# RTI-RoR-wire.net
KiCad netlist of a schematic drawn in EAGLE
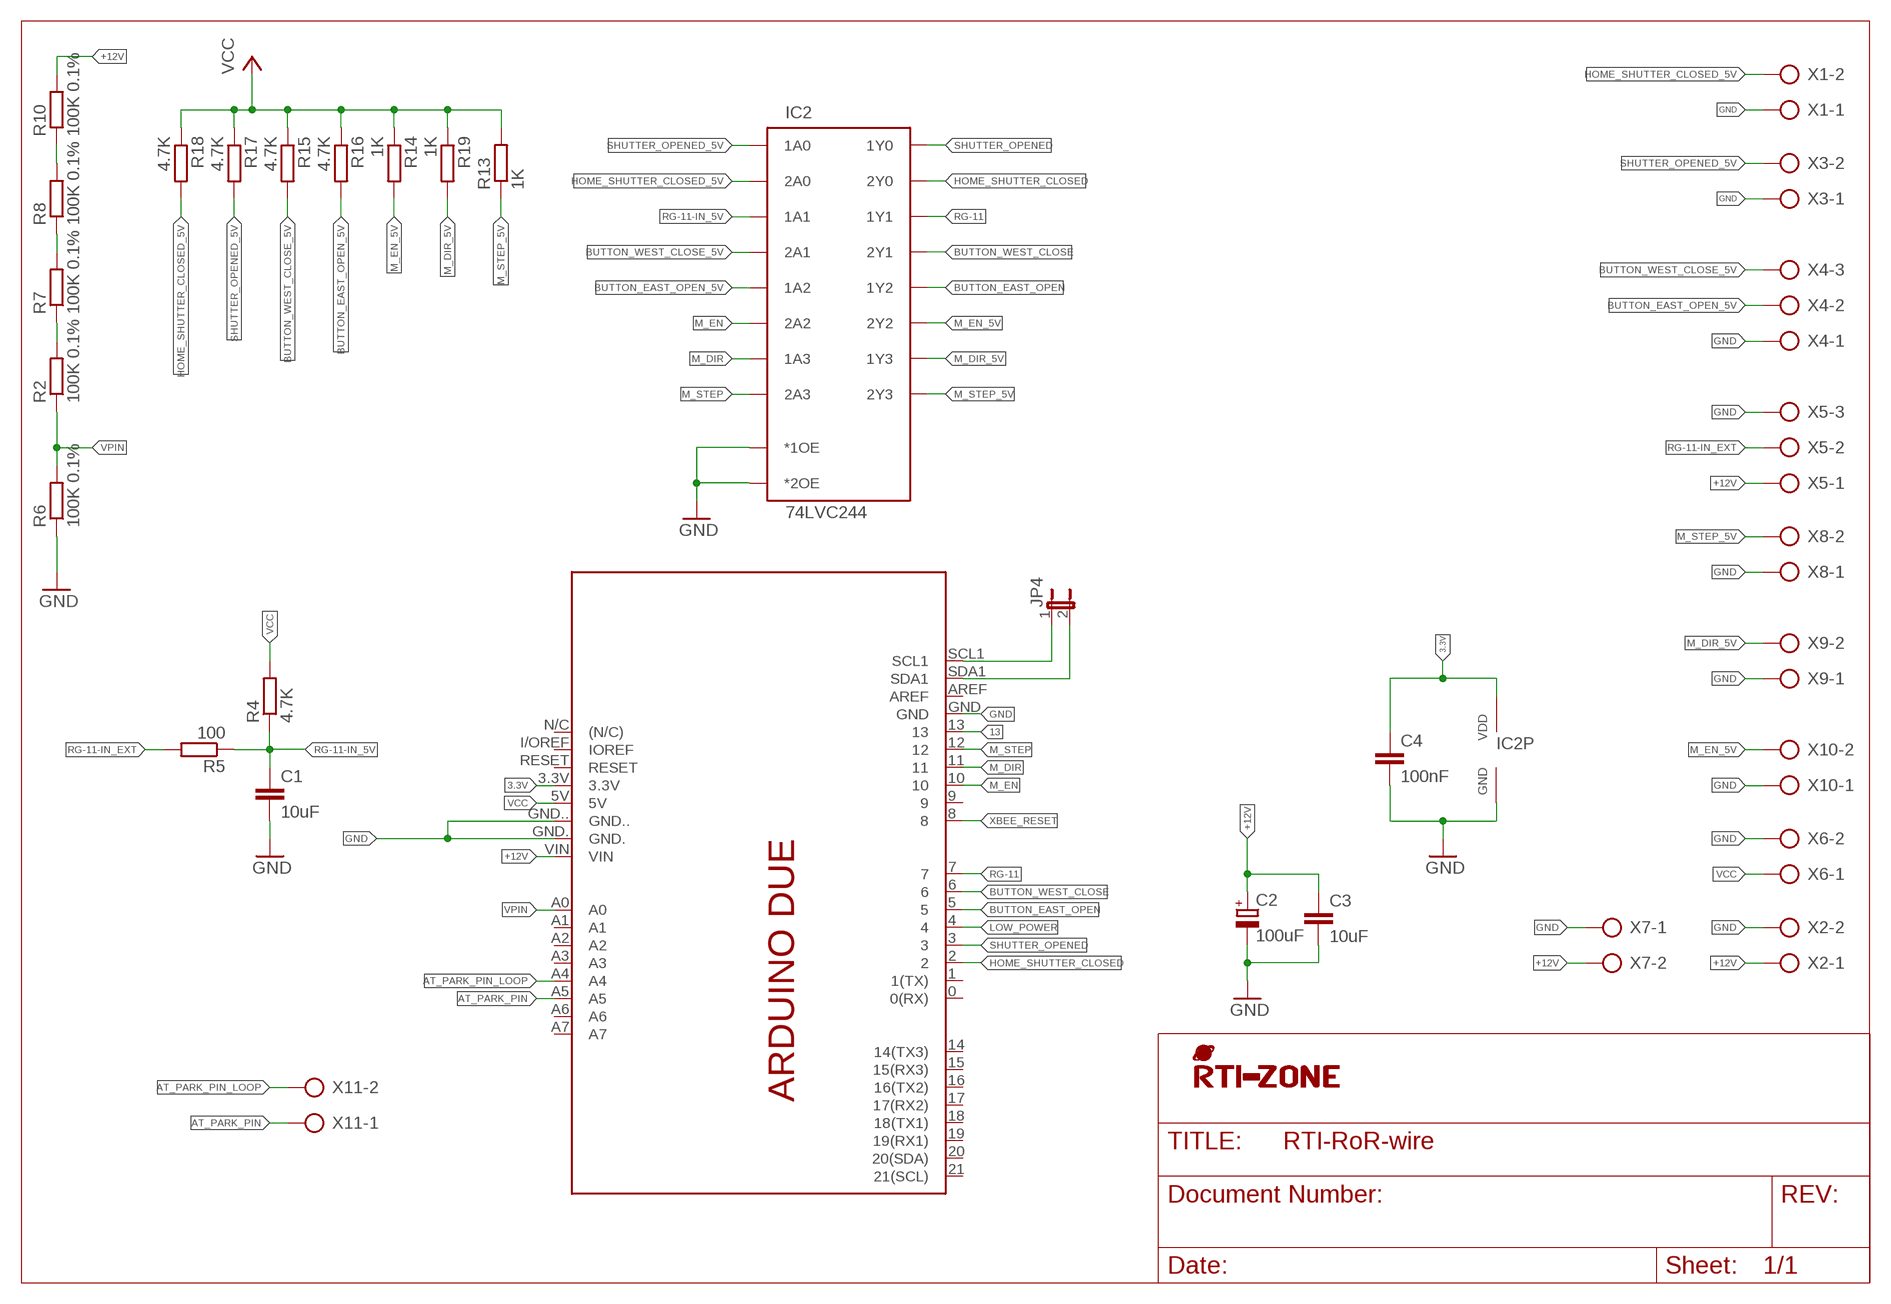
[diagram p0: schematic, sheet 1]

(export (version "E")
  (design (tool "Eeschema 10.0.6"))
  (components
    (comp (ref "C1")
      (value "10uF")
      (footprint "eagle-import:C0805")
      (libsource (lib "eagle-import") (part "C-EU'0805'"))
    )
    (comp (ref "C2")
      (value "100uF")
      (footprint "eagle-import:UD-10X10_NICHICON")
      (libsource (lib "eagle-import") (part "CPOL-EU"))
    )
    (comp (ref "C3")
      (value "10uF")
      (footprint "eagle-import:C0805")
      (libsource (lib "eagle-import") (part "C-EU'0805'"))
    )
    (comp (ref "C4")
      (value "100nF")
      (footprint "eagle-import:C0805")
      (libsource (lib "eagle-import") (part "C-EU'0805'"))
    )
    (comp (ref "IC2")
      (value "74LVC244")
      (footprint "eagle-import:TSSOP20")
      (libsource (lib "eagle-import") (part "74244LVC"))
    )
    (comp (ref "JP4")
      (value "JP1E")
      (footprint "eagle-import:JP1")
      (libsource (lib "eagle-import") (part "JP1E"))
    )
    (comp (ref "PCB1")
      (value "ARDUINO_DUE_SHIELD_SHORT")
      (footprint "eagle-import:ARDUINO_DUE_SHIELD_SHORT")
      (libsource (lib "eagle-import") (part "ARDUINO_DUE_SHIELD_SHORT"))
    )
    (comp (ref "R2")
      (value "100K 0.1%")
      (footprint "eagle-import:R0805")
      (libsource (lib "eagle-import") (part "R-EU'0805'"))
    )
    (comp (ref "R4")
      (value "4.7K")
      (footprint "eagle-import:R0805")
      (libsource (lib "eagle-import") (part "R-EU'0805'"))
    )
    (comp (ref "R5")
      (value "100")
      (footprint "eagle-import:R0805")
      (libsource (lib "eagle-import") (part "R-EU'0805'"))
    )
    (comp (ref "R6")
      (value "100K 0.1%")
      (footprint "eagle-import:R0805")
      (libsource (lib "eagle-import") (part "R-EU'0805'"))
    )
    (comp (ref "R7")
      (value "100K 0.1%")
      (footprint "eagle-import:R0805")
      (libsource (lib "eagle-import") (part "R-EU'0805'"))
    )
    (comp (ref "R8")
      (value "100K 0.1%")
      (footprint "eagle-import:R0805")
      (libsource (lib "eagle-import") (part "R-EU'0805'"))
    )
    (comp (ref "R10")
      (value "100K 0.1%")
      (footprint "eagle-import:R0805")
      (libsource (lib "eagle-import") (part "R-EU'0805'"))
    )
    (comp (ref "R13")
      (value "1K")
      (footprint "eagle-import:R0805")
      (libsource (lib "eagle-import") (part "R-EU'0805'"))
    )
    (comp (ref "R14")
      (value "1K")
      (footprint "eagle-import:R0805")
      (libsource (lib "eagle-import") (part "R-EU'0805'"))
    )
    (comp (ref "R15")
      (value "4.7K")
      (footprint "eagle-import:R0805")
      (libsource (lib "eagle-import") (part "R-EU'0805'"))
    )
    (comp (ref "R16")
      (value "4.7K")
      (footprint "eagle-import:R0805")
      (libsource (lib "eagle-import") (part "R-EU'0805'"))
    )
    (comp (ref "R17")
      (value "4.7K")
      (footprint "eagle-import:R0805")
      (libsource (lib "eagle-import") (part "R-EU'0805'"))
    )
    (comp (ref "R18")
      (value "4.7K")
      (footprint "eagle-import:R0805")
      (libsource (lib "eagle-import") (part "R-EU'0805'"))
    )
    (comp (ref "R19")
      (value "1K")
      (footprint "eagle-import:R0805")
      (libsource (lib "eagle-import") (part "R-EU'0805'"))
    )
    (comp (ref "U$4")
      (value "RTI-LOGO_BIG")
      (footprint "eagle-import:LOGO_BIG")
      (libsource (lib "eagle-import") (part "RTI-LOGO_BIG"))
    )
    (comp (ref "X1")
      (value "AK500/2")
      (footprint "eagle-import:AK500_2")
      (libsource (lib "eagle-import") (part "AK500/2"))
    )
    (comp (ref "X2")
      (value "AK500/2")
      (footprint "eagle-import:AK500_2")
      (libsource (lib "eagle-import") (part "AK500/2"))
    )
    (comp (ref "X3")
      (value "AK500/2")
      (footprint "eagle-import:AK500_2")
      (libsource (lib "eagle-import") (part "AK500/2"))
    )
    (comp (ref "X4")
      (value "AK500/3")
      (footprint "eagle-import:AK500_3")
      (libsource (lib "eagle-import") (part "AK500/3"))
    )
    (comp (ref "X5")
      (value "AK500/3")
      (footprint "eagle-import:AK500_3")
      (libsource (lib "eagle-import") (part "AK500/3"))
    )
    (comp (ref "X6")
      (value "AK500/2")
      (footprint "eagle-import:AK500_2")
      (libsource (lib "eagle-import") (part "AK500/2"))
    )
    (comp (ref "X7")
      (value "AK500/2")
      (footprint "eagle-import:AK500_2")
      (libsource (lib "eagle-import") (part "AK500/2"))
    )
    (comp (ref "X8")
      (value "AK500/2")
      (footprint "eagle-import:AK500_2")
      (libsource (lib "eagle-import") (part "AK500/2"))
    )
    (comp (ref "X9")
      (value "AK500/2")
      (footprint "eagle-import:AK500_2")
      (libsource (lib "eagle-import") (part "AK500/2"))
    )
    (comp (ref "X10")
      (value "AK500/2")
      (footprint "eagle-import:AK500_2")
      (libsource (lib "eagle-import") (part "AK500/2"))
    )
    (comp (ref "X11")
      (value "AK500/2")
      (footprint "eagle-import:AK500_2")
      (libsource (lib "eagle-import") (part "AK500/2"))
    )
  )
  (nets
    (net (code "1") (name "+12V") (class "Default")
      (node (ref "C2") (pin "+") (pinfunction "+_+") (pintype "passive"))
      (node (ref "C3") (pin "1") (pinfunction "1_1") (pintype "passive"))
      (node (ref "PCB1") (pin "VIN") (pinfunction "VIN_VIN") (pintype "bidirectional"))
      (node (ref "R10") (pin "2") (pinfunction "2_2") (pintype "passive"))
      (node (ref "X2") (pin "1") (pinfunction "KL_1") (pintype "passive"))
      (node (ref "X5") (pin "1") (pinfunction "KL_1") (pintype "passive"))
      (node (ref "X7") (pin "2") (pinfunction "KL_2") (pintype "passive"))
    )
    (net (code "2") (name "3.3V") (class "Default")
      (node (ref "C4") (pin "1") (pinfunction "1_1") (pintype "passive"))
      (node (ref "IC2") (pin "P$20") (pinfunction "VDD_P$20") (pintype "power_in"))
      (node (ref "PCB1") (pin "3.3V") (pinfunction "3.3V_3.3V") (pintype "bidirectional"))
    )
    (net (code "3") (name "13") (class "Default")
      (node (ref "PCB1") (pin "13") (pinfunction "13_13") (pintype "bidirectional"))
    )
    (net (code "4") (name "AT_PARK_PIN") (class "Default")
      (node (ref "PCB1") (pin "A5") (pinfunction "A5_A5") (pintype "bidirectional"))
      (node (ref "X11") (pin "1") (pinfunction "KL_1") (pintype "passive"))
    )
    (net (code "5") (name "AT_PARK_PIN_LOOP") (class "Default")
      (node (ref "PCB1") (pin "A4") (pinfunction "A4_A4") (pintype "bidirectional"))
      (node (ref "X11") (pin "2") (pinfunction "KL_2") (pintype "passive"))
    )
    (net (code "6") (name "BUTTON_EAST_OPEN") (class "Default")
      (node (ref "IC2") (pin "P$14") (pinfunction "1Y2_P$14") (pintype "output"))
      (node (ref "PCB1") (pin "5") (pinfunction "5_5") (pintype "bidirectional"))
    )
    (net (code "7") (name "BUTTON_EAST_OPEN_5V") (class "Default")
      (node (ref "IC2") (pin "P$6") (pinfunction "1A2_P$6") (pintype "input"))
      (node (ref "R16") (pin "2") (pinfunction "2_2") (pintype "passive"))
      (node (ref "X4") (pin "2") (pinfunction "KL_2") (pintype "passive"))
    )
    (net (code "8") (name "BUTTON_WEST_CLOSE") (class "Default")
      (node (ref "IC2") (pin "P$5") (pinfunction "2Y1_P$5") (pintype "output"))
      (node (ref "PCB1") (pin "6") (pinfunction "6_6") (pintype "bidirectional"))
    )
    (net (code "9") (name "BUTTON_WEST_CLOSE_5V") (class "Default")
      (node (ref "IC2") (pin "P$15") (pinfunction "2A1_P$15") (pintype "input"))
      (node (ref "R15") (pin "2") (pinfunction "2_2") (pintype "passive"))
      (node (ref "X4") (pin "3") (pinfunction "KL_3") (pintype "passive"))
    )
    (net (code "10") (name "GND") (class "Default")
      (node (ref "C1") (pin "2") (pinfunction "2_2") (pintype "passive"))
      (node (ref "C2") (pin "-") (pinfunction "-_-") (pintype "passive"))
      (node (ref "C3") (pin "2") (pinfunction "2_2") (pintype "passive"))
      (node (ref "C4") (pin "2") (pinfunction "2_2") (pintype "passive"))
      (node (ref "IC2") (pin "P$1") (pinfunction "*1OE_P$1") (pintype "input"))
      (node (ref "IC2") (pin "P$10") (pinfunction "GND_P$10") (pintype "power_in"))
      (node (ref "IC2") (pin "P$19") (pinfunction "*2OE_P$19") (pintype "input"))
      (node (ref "PCB1") (pin "GND") (pinfunction "GND_GND") (pintype "bidirectional"))
      (node (ref "PCB1") (pin "GND.") (pinfunction "GND._GND.") (pintype "bidirectional"))
      (node (ref "PCB1") (pin "GND..") (pinfunction "GND.._GND..") (pintype "bidirectional"))
      (node (ref "R6") (pin "1") (pinfunction "1_1") (pintype "passive"))
      (node (ref "X1") (pin "1") (pinfunction "KL_1") (pintype "passive"))
      (node (ref "X10") (pin "1") (pinfunction "KL_1") (pintype "passive"))
      (node (ref "X2") (pin "2") (pinfunction "KL_2") (pintype "passive"))
      (node (ref "X3") (pin "1") (pinfunction "KL_1") (pintype "passive"))
      (node (ref "X4") (pin "1") (pinfunction "KL_1") (pintype "passive"))
      (node (ref "X5") (pin "3") (pinfunction "KL_3") (pintype "passive"))
      (node (ref "X6") (pin "2") (pinfunction "KL_2") (pintype "passive"))
      (node (ref "X7") (pin "1") (pinfunction "KL_1") (pintype "passive"))
      (node (ref "X8") (pin "1") (pinfunction "KL_1") (pintype "passive"))
      (node (ref "X9") (pin "1") (pinfunction "KL_1") (pintype "passive"))
    )
    (net (code "11") (name "HOME_SHUTTER_CLOSED") (class "Default")
      (node (ref "IC2") (pin "P$3") (pinfunction "2Y0_P$3") (pintype "output"))
      (node (ref "PCB1") (pin "2") (pinfunction "2_2") (pintype "bidirectional"))
    )
    (net (code "12") (name "HOME_SHUTTER_CLOSED_5V") (class "Default")
      (node (ref "IC2") (pin "P$17") (pinfunction "2A0_P$17") (pintype "input"))
      (node (ref "R18") (pin "2") (pinfunction "2_2") (pintype "passive"))
      (node (ref "X1") (pin "2") (pinfunction "KL_2") (pintype "passive"))
    )
    (net (code "13") (name "LOW_POWER") (class "Default")
      (node (ref "PCB1") (pin "4") (pinfunction "4_4") (pintype "bidirectional"))
    )
    (net (code "14") (name "M_DIR") (class "Default")
      (node (ref "IC2") (pin "P$8") (pinfunction "1A3_P$8") (pintype "input"))
      (node (ref "PCB1") (pin "11") (pinfunction "11_11") (pintype "bidirectional"))
    )
    (net (code "15") (name "M_DIR_5V") (class "Default")
      (node (ref "IC2") (pin "P$12") (pinfunction "1Y3_P$12") (pintype "output"))
      (node (ref "R19") (pin "2") (pinfunction "2_2") (pintype "passive"))
      (node (ref "X9") (pin "2") (pinfunction "KL_2") (pintype "passive"))
    )
    (net (code "16") (name "M_EN") (class "Default")
      (node (ref "IC2") (pin "P$13") (pinfunction "2A2_P$13") (pintype "input"))
      (node (ref "PCB1") (pin "10") (pinfunction "10_10") (pintype "bidirectional"))
    )
    (net (code "17") (name "M_EN_5V") (class "Default")
      (node (ref "IC2") (pin "P$7") (pinfunction "2Y2_P$7") (pintype "output"))
      (node (ref "R14") (pin "2") (pinfunction "2_2") (pintype "passive"))
      (node (ref "X10") (pin "2") (pinfunction "KL_2") (pintype "passive"))
    )
    (net (code "18") (name "M_STEP") (class "Default")
      (node (ref "IC2") (pin "P$11") (pinfunction "2A3_P$11") (pintype "input"))
      (node (ref "PCB1") (pin "12") (pinfunction "12_12") (pintype "bidirectional"))
    )
    (net (code "19") (name "M_STEP_5V") (class "Default")
      (node (ref "IC2") (pin "P$9") (pinfunction "2Y3_P$9") (pintype "output"))
      (node (ref "R13") (pin "1") (pinfunction "1_1") (pintype "passive"))
      (node (ref "X8") (pin "2") (pinfunction "KL_2") (pintype "passive"))
    )
    (net (code "20") (name "Net-(JP4-Pad1)") (class "Default")
      (node (ref "JP4") (pin "1") (pinfunction "1_1") (pintype "passive"))
      (node (ref "PCB1") (pin "SCL1") (pinfunction "SCL1_SCL1") (pintype "bidirectional"))
    )
    (net (code "21") (name "Net-(JP4-Pad2)") (class "Default")
      (node (ref "JP4") (pin "2") (pinfunction "2_2") (pintype "passive"))
      (node (ref "PCB1") (pin "SDA1") (pinfunction "SDA1_SDA1") (pintype "bidirectional"))
    )
    (net (code "22") (name "Net-(R2-Pad2)") (class "Default")
      (node (ref "R2") (pin "2") (pinfunction "2_2") (pintype "passive"))
      (node (ref "R7") (pin "1") (pinfunction "1_1") (pintype "passive"))
    )
    (net (code "23") (name "Net-(R7-Pad2)") (class "Default")
      (node (ref "R7") (pin "2") (pinfunction "2_2") (pintype "passive"))
      (node (ref "R8") (pin "1") (pinfunction "1_1") (pintype "passive"))
    )
    (net (code "24") (name "Net-(R10-Pad1)") (class "Default")
      (node (ref "R10") (pin "1") (pinfunction "1_1") (pintype "passive"))
      (node (ref "R8") (pin "2") (pinfunction "2_2") (pintype "passive"))
    )
    (net (code "25") (name "RG-11") (class "Default")
      (node (ref "IC2") (pin "P$16") (pinfunction "1Y1_P$16") (pintype "output"))
      (node (ref "PCB1") (pin "7") (pinfunction "7_7") (pintype "bidirectional"))
    )
    (net (code "26") (name "RG-11-IN_5V") (class "Default")
      (node (ref "C1") (pin "1") (pinfunction "1_1") (pintype "passive"))
      (node (ref "IC2") (pin "P$4") (pinfunction "1A1_P$4") (pintype "input"))
      (node (ref "R4") (pin "1") (pinfunction "1_1") (pintype "passive"))
      (node (ref "R5") (pin "1") (pinfunction "1_1") (pintype "passive"))
    )
    (net (code "27") (name "RG-11-IN_EXT") (class "Default")
      (node (ref "R5") (pin "2") (pinfunction "2_2") (pintype "passive"))
      (node (ref "X5") (pin "2") (pinfunction "KL_2") (pintype "passive"))
    )
    (net (code "28") (name "SHUTTER_OPENED") (class "Default")
      (node (ref "IC2") (pin "P$18") (pinfunction "1Y0_P$18") (pintype "output"))
      (node (ref "PCB1") (pin "3") (pinfunction "3_3") (pintype "bidirectional"))
    )
    (net (code "29") (name "SHUTTER_OPENED_5V") (class "Default")
      (node (ref "IC2") (pin "P$2") (pinfunction "1A0_P$2") (pintype "input"))
      (node (ref "R17") (pin "2") (pinfunction "2_2") (pintype "passive"))
      (node (ref "X3") (pin "2") (pinfunction "KL_2") (pintype "passive"))
    )
    (net (code "30") (name "VCC") (class "Default")
      (node (ref "PCB1") (pin "5V") (pinfunction "5V_5V") (pintype "bidirectional"))
      (node (ref "R13") (pin "2") (pinfunction "2_2") (pintype "passive"))
      (node (ref "R14") (pin "1") (pinfunction "1_1") (pintype "passive"))
      (node (ref "R15") (pin "1") (pinfunction "1_1") (pintype "passive"))
      (node (ref "R16") (pin "1") (pinfunction "1_1") (pintype "passive"))
      (node (ref "R17") (pin "1") (pinfunction "1_1") (pintype "passive"))
      (node (ref "R18") (pin "1") (pinfunction "1_1") (pintype "passive"))
      (node (ref "R19") (pin "1") (pinfunction "1_1") (pintype "passive"))
      (node (ref "R4") (pin "2") (pinfunction "2_2") (pintype "passive"))
      (node (ref "X6") (pin "1") (pinfunction "KL_1") (pintype "passive"))
    )
    (net (code "31") (name "VPIN") (class "Default")
      (node (ref "PCB1") (pin "A0") (pinfunction "A0_A0") (pintype "bidirectional"))
      (node (ref "R2") (pin "1") (pinfunction "1_1") (pintype "passive"))
      (node (ref "R6") (pin "2") (pinfunction "2_2") (pintype "passive"))
    )
    (net (code "32") (name "XBEE_RESET") (class "Default")
      (node (ref "PCB1") (pin "8") (pinfunction "8_8") (pintype "bidirectional"))
    )
    (net (code "33") (name "unconnected-(PCB1-(N{slash}C)-PadN{slash}C)") (class "Default")
      (node (ref "PCB1") (pin "N/C") (pinfunction "(N/C)_N/C") (pintype "bidirectional"))
    )
    (net (code "34") (name "unconnected-(PCB1-0(RX)-Pad0)") (class "Default")
      (node (ref "PCB1") (pin "0") (pinfunction "0(RX)_0") (pintype "bidirectional"))
    )
    (net (code "35") (name "unconnected-(PCB1-1(TX)-Pad1)") (class "Default")
      (node (ref "PCB1") (pin "1") (pinfunction "1(TX)_1") (pintype "bidirectional"))
    )
    (net (code "36") (name "unconnected-(PCB1-14(TX3)-Pad14)") (class "Default")
      (node (ref "PCB1") (pin "14") (pinfunction "14(TX3)_14") (pintype "bidirectional"))
    )
    (net (code "37") (name "unconnected-(PCB1-15(RX3)-Pad15)") (class "Default")
      (node (ref "PCB1") (pin "15") (pinfunction "15(RX3)_15") (pintype "bidirectional"))
    )
    (net (code "38") (name "unconnected-(PCB1-16(TX2)-Pad16)") (class "Default")
      (node (ref "PCB1") (pin "16") (pinfunction "16(TX2)_16") (pintype "bidirectional"))
    )
    (net (code "39") (name "unconnected-(PCB1-17(RX2)-Pad17)") (class "Default")
      (node (ref "PCB1") (pin "17") (pinfunction "17(RX2)_17") (pintype "bidirectional"))
    )
    (net (code "40") (name "unconnected-(PCB1-18(TX1)-Pad18)") (class "Default")
      (node (ref "PCB1") (pin "18") (pinfunction "18(TX1)_18") (pintype "bidirectional"))
    )
    (net (code "41") (name "unconnected-(PCB1-19(RX1)-Pad19)") (class "Default")
      (node (ref "PCB1") (pin "19") (pinfunction "19(RX1)_19") (pintype "bidirectional"))
    )
    (net (code "42") (name "unconnected-(PCB1-20(SDA)-Pad20)") (class "Default")
      (node (ref "PCB1") (pin "20") (pinfunction "20(SDA)_20") (pintype "bidirectional"))
    )
    (net (code "43") (name "unconnected-(PCB1-21(SCL)-Pad21)") (class "Default")
      (node (ref "PCB1") (pin "21") (pinfunction "21(SCL)_21") (pintype "bidirectional"))
    )
    (net (code "44") (name "unconnected-(PCB1-IOREF-PadI{slash}OREF)") (class "Default")
      (node (ref "PCB1") (pin "I/OREF") (pinfunction "IOREF_I/OREF") (pintype "bidirectional"))
    )
    (net (code "45") (name "unconnected-(PCB1-Pad9)") (class "Default")
      (node (ref "PCB1") (pin "9") (pinfunction "9_9") (pintype "bidirectional"))
    )
    (net (code "46") (name "unconnected-(PCB1-PadA1)") (class "Default")
      (node (ref "PCB1") (pin "A1") (pinfunction "A1_A1") (pintype "bidirectional"))
    )
    (net (code "47") (name "unconnected-(PCB1-PadA2)") (class "Default")
      (node (ref "PCB1") (pin "A2") (pinfunction "A2_A2") (pintype "bidirectional"))
    )
    (net (code "48") (name "unconnected-(PCB1-PadA3)") (class "Default")
      (node (ref "PCB1") (pin "A3") (pinfunction "A3_A3") (pintype "bidirectional"))
    )
    (net (code "49") (name "unconnected-(PCB1-PadA6)") (class "Default")
      (node (ref "PCB1") (pin "A6") (pinfunction "A6_A6") (pintype "bidirectional"))
    )
    (net (code "50") (name "unconnected-(PCB1-PadA7)") (class "Default")
      (node (ref "PCB1") (pin "A7") (pinfunction "A7_A7") (pintype "bidirectional"))
    )
    (net (code "51") (name "unconnected-(PCB1-PadAREF)") (class "Default")
      (node (ref "PCB1") (pin "AREF") (pinfunction "AREF_AREF") (pintype "bidirectional"))
    )
    (net (code "52") (name "unconnected-(PCB1-PadRESET)") (class "Default")
      (node (ref "PCB1") (pin "RESET") (pinfunction "RESET_RESET") (pintype "bidirectional"))
    )
  )
)
